# MCU.net
KiCad netlist of a schematic drawn in Altium Designer
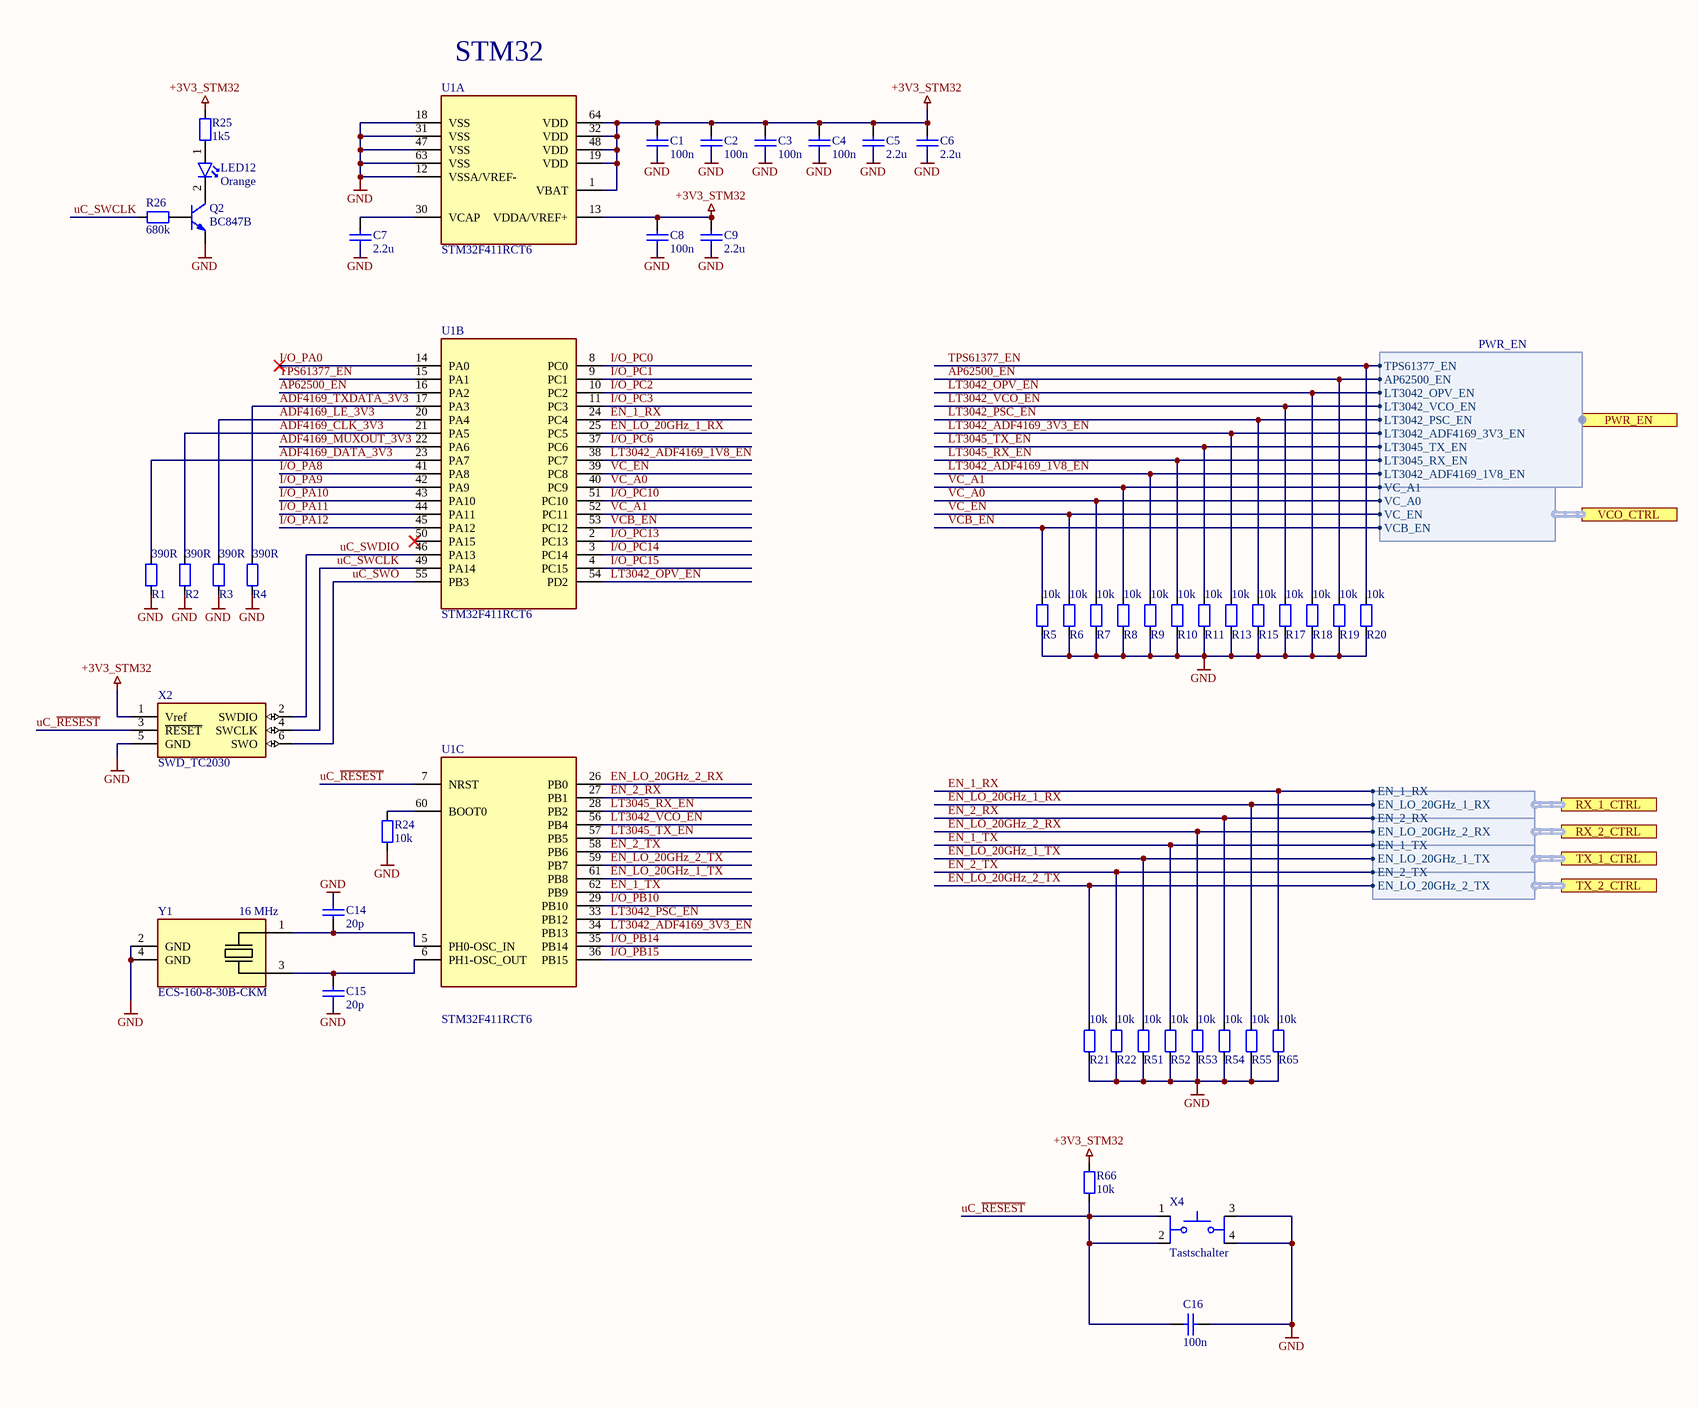
[diagram p0: MCU.SchDoc, left]
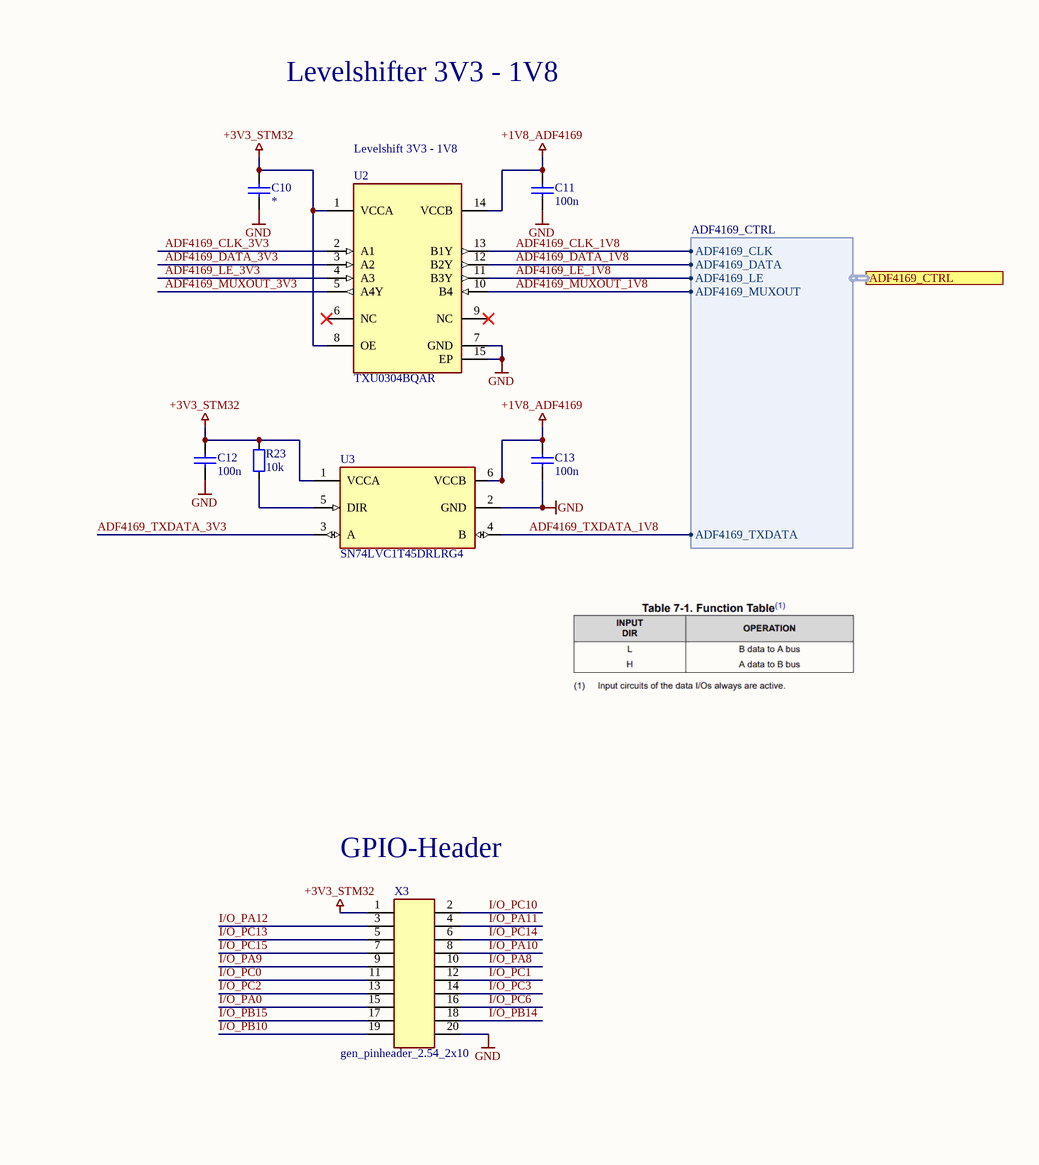
[diagram p1: MCU.SchDoc, right]

(export (version "E")
  (design (tool "Eeschema 10.0.6"))
  (components
    (comp (ref "C1")
      (value "100n")
      (footprint "C_0402_1005Metric_IPC_N")
      (description "Generic MLCC with 0402 Footprint")
      (fields (field (name "TOLERANCE") "10%"))
      (libsource (lib "database_library") (part "Capacitor_unpol"))
    )
    (comp (ref "C2")
      (value "100n")
      (footprint "C_0402_1005Metric_IPC_N")
      (description "Generic MLCC with 0402 Footprint")
      (fields (field (name "TOLERANCE") "10%"))
      (libsource (lib "database_library") (part "Capacitor_unpol"))
    )
    (comp (ref "C3")
      (value "100n")
      (footprint "C_0402_1005Metric_IPC_N")
      (description "Generic MLCC with 0402 Footprint")
      (fields (field (name "TOLERANCE") "10%"))
      (libsource (lib "database_library") (part "Capacitor_unpol"))
    )
    (comp (ref "C4")
      (value "100n")
      (footprint "C_0402_1005Metric_IPC_N")
      (description "Generic MLCC with 0402 Footprint")
      (fields (field (name "TOLERANCE") "10%"))
      (libsource (lib "database_library") (part "Capacitor_unpol"))
    )
    (comp (ref "C5")
      (value "2.2u")
      (footprint "C_0603_1608Metric_IPC_N")
      (description "Generic MLCC with 0603 Footprint")
      (libsource (lib "database_library") (part "Capacitor_unpol"))
    )
    (comp (ref "C6")
      (value "2.2u")
      (footprint "C_0603_1608Metric_IPC_N")
      (description "Generic MLCC with 0603 Footprint")
      (libsource (lib "database_library") (part "Capacitor_unpol"))
    )
    (comp (ref "C7")
      (value "2.2u")
      (footprint "C_0603_1608Metric_IPC_N")
      (description "Generic MLCC with 0603 Footprint")
      (libsource (lib "database_library") (part "Capacitor_unpol"))
    )
    (comp (ref "C8")
      (value "100n")
      (footprint "C_0402_1005Metric_IPC_N")
      (description "Generic MLCC with 0402 Footprint")
      (fields (field (name "TOLERANCE") "10%"))
      (libsource (lib "database_library") (part "Capacitor_unpol"))
    )
    (comp (ref "C9")
      (value "2.2u")
      (footprint "C_0603_1608Metric_IPC_N")
      (description "Generic MLCC with 0603 Footprint")
      (libsource (lib "database_library") (part "Capacitor_unpol"))
    )
    (comp (ref "C10")
      (value "*")
      (footprint "C_0402_1005Metric_IPC_N")
      (description "Generic MLCC with 0402 Footprint")
      (libsource (lib "database_library") (part "Capacitor_unpol"))
    )
    (comp (ref "C11")
      (value "100n")
      (footprint "C_0402_1005Metric_IPC_N")
      (description "Generic MLCC with 0402 Footprint")
      (fields (field (name "TOLERANCE") "10%"))
      (libsource (lib "database_library") (part "Capacitor_unpol"))
    )
    (comp (ref "C12")
      (value "100n")
      (footprint "C_0402_1005Metric_IPC_N")
      (description "Generic MLCC with 0402 Footprint")
      (fields (field (name "TOLERANCE") "10%"))
      (libsource (lib "database_library") (part "Capacitor_unpol"))
    )
    (comp (ref "C13")
      (value "100n")
      (footprint "C_0402_1005Metric_IPC_N")
      (description "Generic MLCC with 0402 Footprint")
      (fields (field (name "TOLERANCE") "10%"))
      (libsource (lib "database_library") (part "Capacitor_unpol"))
    )
    (comp (ref "C14")
      (value "20p")
      (footprint "C_0402_1005Metric_IPC_N")
      (description "Generic MLCC with 0402 Footprint")
      (libsource (lib "database_library") (part "Capacitor_unpol"))
    )
    (comp (ref "C15")
      (value "20p")
      (footprint "C_0402_1005Metric_IPC_N")
      (description "Generic MLCC with 0402 Footprint")
      (libsource (lib "database_library") (part "Capacitor_unpol"))
    )
    (comp (ref "C16")
      (value "100n")
      (footprint "C_0402_1005Metric_IPC_N")
      (description "Generic MLCC with 0402 Footprint")
      (libsource (lib "database_library") (part "Capacitor_unpol"))
    )
    (comp (ref "LED12")
      (value "Orange")
      (footprint "LED_0603_1806Metric_IPC_N")
      (description "MLCC, Low Current, Orange, 2.2V, 20mA, 0603")
      (fields
        (field (name "MANUFACTURER") "Broadcom / Avago")
        (field (name "MANUFACTURER PART NUMBER") "HSMD-C190")
      )
      (libsource (lib "database_library") (part "LED"))
    )
    (comp (ref "Q2")
      (value "BC847B")
      (footprint "SOT-23-3")
      (fields (field (name "MANUFACTURER") "Diotec Semiconductor"))
      (libsource (lib "database_library") (part "NPN"))
    )
    (comp (ref "R1")
      (value "390R")
      (footprint "R_0402_1005Metric_IPC_N")
      (description "Generic Chip Resistor with 0402 Footprint")
      (libsource (lib "database_library") (part "Resistor"))
    )
    (comp (ref "R2")
      (value "390R")
      (footprint "R_0402_1005Metric_IPC_N")
      (description "Generic Chip Resistor with 0402 Footprint")
      (libsource (lib "database_library") (part "Resistor"))
    )
    (comp (ref "R3")
      (value "390R")
      (footprint "R_0402_1005Metric_IPC_N")
      (description "Generic Chip Resistor with 0402 Footprint")
      (libsource (lib "database_library") (part "Resistor"))
    )
    (comp (ref "R4")
      (value "390R")
      (footprint "R_0402_1005Metric_IPC_N")
      (description "Generic Chip Resistor with 0402 Footprint")
      (libsource (lib "database_library") (part "Resistor"))
    )
    (comp (ref "R5")
      (value "10k")
      (footprint "R_0402_1005Metric_IPC_N")
      (description "Generic Chip Resistor with 0402 Footprint")
      (libsource (lib "database_library") (part "Resistor"))
    )
    (comp (ref "R6")
      (value "10k")
      (footprint "R_0402_1005Metric_IPC_N")
      (description "Generic Chip Resistor with 0402 Footprint")
      (libsource (lib "database_library") (part "Resistor"))
    )
    (comp (ref "R7")
      (value "10k")
      (footprint "R_0402_1005Metric_IPC_N")
      (description "Generic Chip Resistor with 0402 Footprint")
      (libsource (lib "database_library") (part "Resistor"))
    )
    (comp (ref "R8")
      (value "10k")
      (footprint "R_0402_1005Metric_IPC_N")
      (description "Generic Chip Resistor with 0402 Footprint")
      (libsource (lib "database_library") (part "Resistor"))
    )
    (comp (ref "R9")
      (value "10k")
      (footprint "R_0402_1005Metric_IPC_N")
      (description "Generic Chip Resistor with 0402 Footprint")
      (libsource (lib "database_library") (part "Resistor"))
    )
    (comp (ref "R10")
      (value "10k")
      (footprint "R_0402_1005Metric_IPC_N")
      (description "Generic Chip Resistor with 0402 Footprint")
      (libsource (lib "database_library") (part "Resistor"))
    )
    (comp (ref "R11")
      (value "10k")
      (footprint "R_0402_1005Metric_IPC_N")
      (description "Generic Chip Resistor with 0402 Footprint")
      (libsource (lib "database_library") (part "Resistor"))
    )
    (comp (ref "R13")
      (value "10k")
      (footprint "R_0402_1005Metric_IPC_N")
      (description "Generic Chip Resistor with 0402 Footprint")
      (libsource (lib "database_library") (part "Resistor"))
    )
    (comp (ref "R15")
      (value "10k")
      (footprint "R_0402_1005Metric_IPC_N")
      (description "Generic Chip Resistor with 0402 Footprint")
      (libsource (lib "database_library") (part "Resistor"))
    )
    (comp (ref "R17")
      (value "10k")
      (footprint "R_0402_1005Metric_IPC_N")
      (description "Generic Chip Resistor with 0402 Footprint")
      (libsource (lib "database_library") (part "Resistor"))
    )
    (comp (ref "R18")
      (value "10k")
      (footprint "R_0402_1005Metric_IPC_N")
      (description "Generic Chip Resistor with 0402 Footprint")
      (libsource (lib "database_library") (part "Resistor"))
    )
    (comp (ref "R19")
      (value "10k")
      (footprint "R_0402_1005Metric_IPC_N")
      (description "Generic Chip Resistor with 0402 Footprint")
      (libsource (lib "database_library") (part "Resistor"))
    )
    (comp (ref "R20")
      (value "10k")
      (footprint "R_0402_1005Metric_IPC_N")
      (description "Generic Chip Resistor with 0402 Footprint")
      (libsource (lib "database_library") (part "Resistor"))
    )
    (comp (ref "R21")
      (value "10k")
      (footprint "R_0402_1005Metric_IPC_N")
      (description "Generic Chip Resistor with 0402 Footprint")
      (libsource (lib "database_library") (part "Resistor"))
    )
    (comp (ref "R22")
      (value "10k")
      (footprint "R_0402_1005Metric_IPC_N")
      (description "Generic Chip Resistor with 0402 Footprint")
      (libsource (lib "database_library") (part "Resistor"))
    )
    (comp (ref "R23")
      (value "10k")
      (footprint "R_0402_1005Metric_IPC_N")
      (description "Generic Chip Resistor with 0402 Footprint")
      (libsource (lib "database_library") (part "Resistor"))
    )
    (comp (ref "R24")
      (value "10k")
      (footprint "R_0402_1005Metric_IPC_N")
      (description "Generic Chip Resistor with 0402 Footprint")
      (libsource (lib "database_library") (part "Resistor"))
    )
    (comp (ref "R25")
      (value "1k5")
      (footprint "R_0402_1005Metric_IPC_N")
      (description "Generic Chip Resistor with 0402 Footprint")
      (libsource (lib "database_library") (part "Resistor"))
    )
    (comp (ref "R26")
      (value "680k")
      (footprint "R_0402_1005Metric_IPC_N")
      (description "Generic Chip Resistor with 0402 Footprint")
      (libsource (lib "database_library") (part "Resistor"))
    )
    (comp (ref "R51")
      (value "10k")
      (footprint "R_0402_1005Metric_IPC_N")
      (description "Generic Chip Resistor with 0402 Footprint")
      (libsource (lib "database_library") (part "Resistor"))
    )
    (comp (ref "R52")
      (value "10k")
      (footprint "R_0402_1005Metric_IPC_N")
      (description "Generic Chip Resistor with 0402 Footprint")
      (libsource (lib "database_library") (part "Resistor"))
    )
    (comp (ref "R53")
      (value "10k")
      (footprint "R_0402_1005Metric_IPC_N")
      (description "Generic Chip Resistor with 0402 Footprint")
      (libsource (lib "database_library") (part "Resistor"))
    )
    (comp (ref "R54")
      (value "10k")
      (footprint "R_0402_1005Metric_IPC_N")
      (description "Generic Chip Resistor with 0402 Footprint")
      (libsource (lib "database_library") (part "Resistor"))
    )
    (comp (ref "R55")
      (value "10k")
      (footprint "R_0402_1005Metric_IPC_N")
      (description "Generic Chip Resistor with 0402 Footprint")
      (libsource (lib "database_library") (part "Resistor"))
    )
    (comp (ref "R65")
      (value "10k")
      (footprint "R_0402_1005Metric_IPC_N")
      (description "Generic Chip Resistor with 0402 Footprint")
      (libsource (lib "database_library") (part "Resistor"))
    )
    (comp (ref "R66")
      (value "10k")
      (footprint "R_0402_1005Metric_IPC_N")
      (description "Generic Chip Resistor with 0402 Footprint")
      (libsource (lib "database_library") (part "Resistor"))
    )
    (comp (ref "U1")
      (value "STM32F411RCT6")
      (footprint "QFP50P1200X1200X160-64N")
      (fields
        (field (name "MOUSER PART NUMBER") "511-STM32F411RCT6")
        (field (name "MANUFACTURER") "STMicroelectronics")
      )
      (libsource (lib "database_library") (part "STM32F411RCT6"))
    )
    (comp (ref "U2")
      (value "TXU0304BQAR")
      (footprint "WQFN-14-1EP_2.5x3mm_P0.5mm_EP1.0x1.5mm_IPC_N")
      (fields (field (name "MANUFACTURER") "Texas Instruments"))
      (libsource (lib "database_library") (part "TXU0304BQAR"))
    )
    (comp (ref "U3")
      (value "SN74LVC1T45DRLRG4")
      (footprint "SOTFL50P160X60-6N")
      (fields (field (name "MANUFACTURER") "Texas Instruments"))
      (libsource (lib "database_library") (part "SN74LVC1T45DRLRG4"))
    )
    (comp (ref "X2")
      (value "SWD_TC2030")
      (footprint "Tag-Connect_TC2030-IDC-FP_2x03_P1.27mm_Vertical")
      (fields
        (field (name "MANUFACTURER PART NUMBER") "SWD TC2030")
        (field (name "MANUFACTURER") "Tag-Connect")
      )
      (libsource (lib "database_library") (part "SWD_TC2030"))
    )
    (comp (ref "X3")
      (value "gen_pinheader_2.54_2x10")
      (footprint "Pinheader_2.54_2x10")
      (fields
        (field (name "MANUFACTURER PART NUMBER") "TSW-110-07-G-D")
        (field (name "MANUFACTURER") "Samtec")
      )
      (libsource (lib "database_library") (part "gen_pinheader_2.54_2x10"))
    )
    (comp (ref "X4")
      (value "Tastschalter")
      (footprint "TL3301AF160QG")
      (fields
        (field (name "MANUFACTURER PART NUMBER") "TL3301AF160QG")
        (field (name "MANUFACTURER") "E-Switch")
      )
      (libsource (lib "database_library") (part "Tastschalter"))
    )
    (comp (ref "Y1")
      (value "ECS-160-8-30B-CKM")
      (footprint "XTAL_SMD_5032_4Pin_5x3.2mm")
      (fields (field (name "MANUFACTURER") "ECS"))
      (libsource (lib "database_library") (part "XTAL_PIN1/3_GND2/4"))
    )
  )
  (nets
    (net (code "8") (name "+1V8_ADF4169") (class "Default")
      (node (ref "C11") (pin "2") (pinfunction "2_2") (pintype "passive"))
      (node (ref "C13") (pin "2") (pinfunction "2_2") (pintype "passive"))
      (node (ref "U2") (pin "14") (pinfunction "VCCB_14") (pintype "passive"))
      (node (ref "U3") (pin "6") (pinfunction "VCCB_6") (pintype "power_in"))
    )
    (net (code "9") (name "+3V3_STM32") (class "Default")
      (node (ref "C1") (pin "2") (pinfunction "2_2") (pintype "passive"))
      (node (ref "C10") (pin "2") (pinfunction "2_2") (pintype "passive"))
      (node (ref "C12") (pin "2") (pinfunction "2_2") (pintype "passive"))
      (node (ref "C2") (pin "2") (pinfunction "2_2") (pintype "passive"))
      (node (ref "C3") (pin "2") (pinfunction "2_2") (pintype "passive"))
      (node (ref "C4") (pin "2") (pinfunction "2_2") (pintype "passive"))
      (node (ref "C5") (pin "2") (pinfunction "2_2") (pintype "passive"))
      (node (ref "C6") (pin "2") (pinfunction "2_2") (pintype "passive"))
      (node (ref "C8") (pin "2") (pinfunction "2_2") (pintype "passive"))
      (node (ref "C9") (pin "2") (pinfunction "2_2") (pintype "passive"))
      (node (ref "R23") (pin "1") (pinfunction "1_1") (pintype "passive"))
      (node (ref "R25") (pin "2") (pinfunction "2_2") (pintype "passive"))
      (node (ref "R66") (pin "2") (pinfunction "2_2") (pintype "passive"))
      (node (ref "U1") (pin "1") (pinfunction "VBAT_1") (pintype "passive"))
      (node (ref "U1") (pin "13") (pinfunction "VDDA/VREF+_13") (pintype "passive"))
      (node (ref "U1") (pin "19") (pinfunction "VDD_19") (pintype "passive"))
      (node (ref "U1") (pin "32") (pinfunction "VDD_32") (pintype "passive"))
      (node (ref "U1") (pin "48") (pinfunction "VDD_48") (pintype "passive"))
      (node (ref "U1") (pin "64") (pinfunction "VDD_64") (pintype "passive"))
      (node (ref "U2") (pin "1") (pinfunction "VCCA_1") (pintype "passive"))
      (node (ref "U2") (pin "8") (pinfunction "OE_8") (pintype "passive"))
      (node (ref "U3") (pin "1") (pinfunction "VCCA_1") (pintype "power_in"))
      (node (ref "X2") (pin "1") (pinfunction "Vref_1") (pintype "passive"))
      (node (ref "X3") (pin "1") (pintype "passive"))
    )
    (net (code "10") (name "/ADF4169_CLK_1V8") (class "Default")
      (node (ref "U2") (pin "13") (pinfunction "B1Y_13") (pintype "output"))
    )
    (net (code "11") (name "/ADF4169_CLK_3V3") (class "Default")
      (node (ref "R2") (pin "2") (pinfunction "2_2") (pintype "passive"))
      (node (ref "U1") (pin "21") (pinfunction "PA5_21") (pintype "passive"))
      (node (ref "U2") (pin "2") (pinfunction "A1_2") (pintype "input"))
    )
    (net (code "12") (name "/ADF4169_DATA_1V8") (class "Default")
      (node (ref "U2") (pin "12") (pinfunction "B2Y_12") (pintype "output"))
    )
    (net (code "13") (name "/ADF4169_DATA_3V3") (class "Default")
      (node (ref "R1") (pin "2") (pinfunction "2_2") (pintype "passive"))
      (node (ref "U1") (pin "23") (pinfunction "PA7_23") (pintype "passive"))
      (node (ref "U2") (pin "3") (pinfunction "A2_3") (pintype "input"))
    )
    (net (code "14") (name "/ADF4169_LE_1V8") (class "Default")
      (node (ref "U2") (pin "11") (pinfunction "B3Y_11") (pintype "output"))
    )
    (net (code "15") (name "/ADF4169_LE_3V3") (class "Default")
      (node (ref "R3") (pin "2") (pinfunction "2_2") (pintype "passive"))
      (node (ref "U1") (pin "20") (pinfunction "PA4_20") (pintype "passive"))
      (node (ref "U2") (pin "4") (pinfunction "A3_4") (pintype "input"))
    )
    (net (code "16") (name "/ADF4169_MUXOUT_1V8") (class "Default")
      (node (ref "U2") (pin "10") (pinfunction "B4_10") (pintype "input"))
    )
    (net (code "17") (name "/ADF4169_MUXOUT_3V3") (class "Default")
      (node (ref "U1") (pin "22") (pinfunction "PA6_22") (pintype "passive"))
      (node (ref "U2") (pin "5") (pinfunction "A4Y_5") (pintype "output"))
    )
    (net (code "18") (name "/ADF4169_TXDATA_1V8") (class "Default")
      (node (ref "U3") (pin "4") (pinfunction "B_4") (pintype "bidirectional"))
    )
    (net (code "19") (name "/ADF4169_TXDATA_3V3") (class "Default")
      (node (ref "R4") (pin "2") (pinfunction "2_2") (pintype "passive"))
      (node (ref "U1") (pin "17") (pinfunction "PA3_17") (pintype "passive"))
      (node (ref "U3") (pin "3") (pinfunction "A_3") (pintype "bidirectional"))
    )
    (net (code "20") (name "/AP62500_EN") (class "Default")
      (node (ref "R19") (pin "2") (pinfunction "2_2") (pintype "passive"))
      (node (ref "U1") (pin "16") (pinfunction "PA2_16") (pintype "passive"))
    )
    (net (code "21") (name "/EN_1_RX") (class "Default")
      (node (ref "R65") (pin "2") (pinfunction "2_2") (pintype "passive"))
      (node (ref "U1") (pin "24") (pinfunction "PC4_24") (pintype "passive"))
    )
    (net (code "22") (name "/EN_1_TX") (class "Default")
      (node (ref "R52") (pin "2") (pinfunction "2_2") (pintype "passive"))
      (node (ref "U1") (pin "62") (pinfunction "PB9_62") (pintype "passive"))
    )
    (net (code "23") (name "/EN_2_RX") (class "Default")
      (node (ref "R54") (pin "2") (pinfunction "2_2") (pintype "passive"))
      (node (ref "U1") (pin "27") (pinfunction "PB1_27") (pintype "passive"))
    )
    (net (code "24") (name "/EN_2_TX") (class "Default")
      (node (ref "R22") (pin "2") (pinfunction "2_2") (pintype "passive"))
      (node (ref "U1") (pin "58") (pinfunction "PB6_58") (pintype "passive"))
    )
    (net (code "25") (name "/EN_LO_20GHz_1_RX") (class "Default")
      (node (ref "R55") (pin "2") (pinfunction "2_2") (pintype "passive"))
      (node (ref "U1") (pin "25") (pinfunction "PC5_25") (pintype "passive"))
    )
    (net (code "26") (name "/EN_LO_20GHz_1_TX") (class "Default")
      (node (ref "R51") (pin "2") (pinfunction "2_2") (pintype "passive"))
      (node (ref "U1") (pin "61") (pinfunction "PB8_61") (pintype "passive"))
    )
    (net (code "27") (name "/EN_LO_20GHz_2_RX") (class "Default")
      (node (ref "R53") (pin "2") (pinfunction "2_2") (pintype "passive"))
      (node (ref "U1") (pin "26") (pinfunction "PB0_26") (pintype "passive"))
    )
    (net (code "28") (name "/EN_LO_20GHz_2_TX") (class "Default")
      (node (ref "R21") (pin "2") (pinfunction "2_2") (pintype "passive"))
      (node (ref "U1") (pin "59") (pinfunction "PB7_59") (pintype "passive"))
    )
    (net (code "29") (name "/I{slash}O_PA0") (class "Default")
      (node (ref "U1") (pin "14") (pinfunction "PA0_14") (pintype "passive"))
      (node (ref "X3") (pin "15") (pintype "passive"))
    )
    (net (code "30") (name "/I{slash}O_PA8") (class "Default")
      (node (ref "U1") (pin "41") (pinfunction "PA8_41") (pintype "passive"))
      (node (ref "X3") (pin "10") (pintype "passive"))
    )
    (net (code "31") (name "/I{slash}O_PA9") (class "Default")
      (node (ref "U1") (pin "42") (pinfunction "PA9_42") (pintype "passive"))
      (node (ref "X3") (pin "9") (pintype "passive"))
    )
    (net (code "32") (name "/I{slash}O_PA10") (class "Default")
      (node (ref "U1") (pin "43") (pinfunction "PA10_43") (pintype "passive"))
      (node (ref "X3") (pin "8") (pintype "passive"))
    )
    (net (code "33") (name "/I{slash}O_PA11") (class "Default")
      (node (ref "U1") (pin "44") (pinfunction "PA11_44") (pintype "passive"))
      (node (ref "X3") (pin "4") (pintype "passive"))
    )
    (net (code "34") (name "/I{slash}O_PA12") (class "Default")
      (node (ref "U1") (pin "45") (pinfunction "PA12_45") (pintype "passive"))
      (node (ref "X3") (pin "3") (pintype "passive"))
    )
    (net (code "35") (name "/I{slash}O_PB10") (class "Default")
      (node (ref "U1") (pin "29") (pinfunction "PB10_29") (pintype "passive"))
      (node (ref "X3") (pin "19") (pintype "passive"))
    )
    (net (code "36") (name "/I{slash}O_PB14") (class "Default")
      (node (ref "U1") (pin "35") (pinfunction "PB14_35") (pintype "passive"))
      (node (ref "X3") (pin "18") (pintype "passive"))
    )
    (net (code "37") (name "/I{slash}O_PB15") (class "Default")
      (node (ref "U1") (pin "36") (pinfunction "PB15_36") (pintype "passive"))
      (node (ref "X3") (pin "17") (pintype "passive"))
    )
    (net (code "38") (name "/I{slash}O_PC0") (class "Default")
      (node (ref "U1") (pin "8") (pinfunction "PC0_8") (pintype "passive"))
      (node (ref "X3") (pin "11") (pintype "passive"))
    )
    (net (code "39") (name "/I{slash}O_PC1") (class "Default")
      (node (ref "U1") (pin "9") (pinfunction "PC1_9") (pintype "passive"))
      (node (ref "X3") (pin "12") (pintype "passive"))
    )
    (net (code "40") (name "/I{slash}O_PC2") (class "Default")
      (node (ref "U1") (pin "10") (pinfunction "PC2_10") (pintype "passive"))
      (node (ref "X3") (pin "13") (pintype "passive"))
    )
    (net (code "41") (name "/I{slash}O_PC3") (class "Default")
      (node (ref "U1") (pin "11") (pinfunction "PC3_11") (pintype "passive"))
      (node (ref "X3") (pin "14") (pintype "passive"))
    )
    (net (code "42") (name "/I{slash}O_PC6") (class "Default")
      (node (ref "U1") (pin "37") (pinfunction "PC6_37") (pintype "passive"))
      (node (ref "X3") (pin "16") (pintype "passive"))
    )
    (net (code "43") (name "/I{slash}O_PC10") (class "Default")
      (node (ref "U1") (pin "51") (pinfunction "PC10_51") (pintype "passive"))
      (node (ref "X3") (pin "2") (pintype "passive"))
    )
    (net (code "44") (name "/I{slash}O_PC13") (class "Default")
      (node (ref "U1") (pin "2") (pinfunction "PC13_2") (pintype "passive"))
      (node (ref "X3") (pin "5") (pintype "passive"))
    )
    (net (code "45") (name "/I{slash}O_PC14") (class "Default")
      (node (ref "U1") (pin "3") (pinfunction "PC14_3") (pintype "passive"))
      (node (ref "X3") (pin "6") (pintype "passive"))
    )
    (net (code "46") (name "/I{slash}O_PC15") (class "Default")
      (node (ref "U1") (pin "4") (pinfunction "PC15_4") (pintype "passive"))
      (node (ref "X3") (pin "7") (pintype "passive"))
    )
    (net (code "47") (name "/LT3042_ADF4169_1V8_EN") (class "Default")
      (node (ref "R9") (pin "2") (pinfunction "2_2") (pintype "passive"))
      (node (ref "U1") (pin "38") (pinfunction "PC7_38") (pintype "passive"))
    )
    (net (code "48") (name "/LT3042_ADF4169_3V3_EN") (class "Default")
      (node (ref "R13") (pin "2") (pinfunction "2_2") (pintype "passive"))
      (node (ref "U1") (pin "34") (pinfunction "PB13_34") (pintype "passive"))
    )
    (net (code "49") (name "/LT3042_OPV_EN") (class "Default")
      (node (ref "R18") (pin "2") (pinfunction "2_2") (pintype "passive"))
      (node (ref "U1") (pin "54") (pinfunction "PD2_54") (pintype "passive"))
    )
    (net (code "50") (name "/LT3042_PSC_EN") (class "Default")
      (node (ref "R15") (pin "2") (pinfunction "2_2") (pintype "passive"))
      (node (ref "U1") (pin "33") (pinfunction "PB12_33") (pintype "passive"))
    )
    (net (code "51") (name "/LT3042_VCO_EN") (class "Default")
      (node (ref "R17") (pin "2") (pinfunction "2_2") (pintype "passive"))
      (node (ref "U1") (pin "56") (pinfunction "PB4_56") (pintype "passive"))
    )
    (net (code "52") (name "/LT3045_RX_EN") (class "Default")
      (node (ref "R10") (pin "2") (pinfunction "2_2") (pintype "passive"))
      (node (ref "U1") (pin "28") (pinfunction "PB2_28") (pintype "passive"))
    )
    (net (code "53") (name "/LT3045_TX_EN") (class "Default")
      (node (ref "R11") (pin "2") (pinfunction "2_2") (pintype "passive"))
      (node (ref "U1") (pin "57") (pinfunction "PB5_57") (pintype "passive"))
    )
    (net (code "54") (name "/TPS61377_EN") (class "Default")
      (node (ref "R20") (pin "2") (pinfunction "2_2") (pintype "passive"))
      (node (ref "U1") (pin "15") (pinfunction "PA1_15") (pintype "passive"))
    )
    (net (code "55") (name "/VCB_EN") (class "Default")
      (node (ref "R5") (pin "2") (pinfunction "2_2") (pintype "passive"))
      (node (ref "U1") (pin "53") (pinfunction "PC12_53") (pintype "passive"))
    )
    (net (code "56") (name "/VC_A0") (class "Default")
      (node (ref "R7") (pin "2") (pinfunction "2_2") (pintype "passive"))
      (node (ref "U1") (pin "40") (pinfunction "PC9_40") (pintype "passive"))
    )
    (net (code "57") (name "/VC_A1") (class "Default")
      (node (ref "R8") (pin "2") (pinfunction "2_2") (pintype "passive"))
      (node (ref "U1") (pin "52") (pinfunction "PC11_52") (pintype "passive"))
    )
    (net (code "58") (name "/VC_EN") (class "Default")
      (node (ref "R6") (pin "2") (pinfunction "2_2") (pintype "passive"))
      (node (ref "U1") (pin "39") (pinfunction "PC8_39") (pintype "passive"))
    )
    (net (code "59") (name "/uC_SWCLK") (class "Default")
      (node (ref "R26") (pin "1") (pinfunction "1_1") (pintype "passive"))
      (node (ref "U1") (pin "49") (pinfunction "PA14_49") (pintype "passive"))
      (node (ref "X2") (pin "4") (pinfunction "SWCLK_4") (pintype "bidirectional"))
    )
    (net (code "60") (name "/uC_SWDIO") (class "Default")
      (node (ref "U1") (pin "46") (pinfunction "PA13_46") (pintype "passive"))
      (node (ref "X2") (pin "2") (pinfunction "SWDIO_2") (pintype "bidirectional"))
    )
    (net (code "61") (name "/uC_SWO") (class "Default")
      (node (ref "U1") (pin "55") (pinfunction "PB3_55") (pintype "passive"))
      (node (ref "X2") (pin "6") (pinfunction "SWO_6") (pintype "bidirectional"))
    )
    (net (code "62") (name "/uC_~{RESEST}") (class "Default")
      (node (ref "C16") (pin "1") (pinfunction "1_1") (pintype "passive"))
      (node (ref "R66") (pin "1") (pinfunction "1_1") (pintype "passive"))
      (node (ref "U1") (pin "7") (pinfunction "NRST_7") (pintype "passive"))
      (node (ref "X2") (pin "3") (pinfunction "~{RESET}_3") (pintype "passive"))
      (node (ref "X4") (pin "1") (pinfunction "1_1") (pintype "passive"))
      (node (ref "X4") (pin "2") (pinfunction "2_2") (pintype "passive"))
    )
    (net (code "70") (name "GND") (class "Default")
      (node (ref "C1") (pin "1") (pinfunction "1_1") (pintype "passive"))
      (node (ref "C10") (pin "1") (pinfunction "1_1") (pintype "passive"))
      (node (ref "C11") (pin "1") (pinfunction "1_1") (pintype "passive"))
      (node (ref "C12") (pin "1") (pinfunction "1_1") (pintype "passive"))
      (node (ref "C13") (pin "1") (pinfunction "1_1") (pintype "passive"))
      (node (ref "C14") (pin "2") (pinfunction "2_2") (pintype "passive"))
      (node (ref "C15") (pin "1") (pinfunction "1_1") (pintype "passive"))
      (node (ref "C16") (pin "2") (pinfunction "2_2") (pintype "passive"))
      (node (ref "C2") (pin "1") (pinfunction "1_1") (pintype "passive"))
      (node (ref "C3") (pin "1") (pinfunction "1_1") (pintype "passive"))
      (node (ref "C4") (pin "1") (pinfunction "1_1") (pintype "passive"))
      (node (ref "C5") (pin "1") (pinfunction "1_1") (pintype "passive"))
      (node (ref "C6") (pin "1") (pinfunction "1_1") (pintype "passive"))
      (node (ref "C7") (pin "1") (pinfunction "1_1") (pintype "passive"))
      (node (ref "C8") (pin "1") (pinfunction "1_1") (pintype "passive"))
      (node (ref "C9") (pin "1") (pinfunction "1_1") (pintype "passive"))
      (node (ref "Q2") (pin "2") (pinfunction "E_2") (pintype "passive"))
      (node (ref "R1") (pin "1") (pinfunction "1_1") (pintype "passive"))
      (node (ref "R10") (pin "1") (pinfunction "1_1") (pintype "passive"))
      (node (ref "R11") (pin "1") (pinfunction "1_1") (pintype "passive"))
      (node (ref "R13") (pin "1") (pinfunction "1_1") (pintype "passive"))
      (node (ref "R15") (pin "1") (pinfunction "1_1") (pintype "passive"))
      (node (ref "R17") (pin "1") (pinfunction "1_1") (pintype "passive"))
      (node (ref "R18") (pin "1") (pinfunction "1_1") (pintype "passive"))
      (node (ref "R19") (pin "1") (pinfunction "1_1") (pintype "passive"))
      (node (ref "R2") (pin "1") (pinfunction "1_1") (pintype "passive"))
      (node (ref "R20") (pin "1") (pinfunction "1_1") (pintype "passive"))
      (node (ref "R21") (pin "1") (pinfunction "1_1") (pintype "passive"))
      (node (ref "R22") (pin "1") (pinfunction "1_1") (pintype "passive"))
      (node (ref "R24") (pin "2") (pinfunction "2_2") (pintype "passive"))
      (node (ref "R3") (pin "1") (pinfunction "1_1") (pintype "passive"))
      (node (ref "R4") (pin "1") (pinfunction "1_1") (pintype "passive"))
      (node (ref "R5") (pin "1") (pinfunction "1_1") (pintype "passive"))
      (node (ref "R51") (pin "1") (pinfunction "1_1") (pintype "passive"))
      (node (ref "R52") (pin "1") (pinfunction "1_1") (pintype "passive"))
      (node (ref "R53") (pin "1") (pinfunction "1_1") (pintype "passive"))
      (node (ref "R54") (pin "1") (pinfunction "1_1") (pintype "passive"))
      (node (ref "R55") (pin "1") (pinfunction "1_1") (pintype "passive"))
      (node (ref "R6") (pin "1") (pinfunction "1_1") (pintype "passive"))
      (node (ref "R65") (pin "1") (pinfunction "1_1") (pintype "passive"))
      (node (ref "R7") (pin "1") (pinfunction "1_1") (pintype "passive"))
      (node (ref "R8") (pin "1") (pinfunction "1_1") (pintype "passive"))
      (node (ref "R9") (pin "1") (pinfunction "1_1") (pintype "passive"))
      (node (ref "U1") (pin "12") (pinfunction "VSSA/VREF-_12") (pintype "passive"))
      (node (ref "U1") (pin "18") (pinfunction "VSS_18") (pintype "passive"))
      (node (ref "U1") (pin "31") (pinfunction "VSS_31") (pintype "passive"))
      (node (ref "U1") (pin "47") (pinfunction "VSS_47") (pintype "passive"))
      (node (ref "U1") (pin "63") (pinfunction "VSS_63") (pintype "passive"))
      (node (ref "U2") (pin "15") (pinfunction "EP_15") (pintype "passive"))
      (node (ref "U2") (pin "7") (pinfunction "GND_7") (pintype "passive"))
      (node (ref "U3") (pin "2") (pinfunction "GND_2") (pintype "power_in"))
      (node (ref "X2") (pin "5") (pinfunction "GND_5") (pintype "passive"))
      (node (ref "X3") (pin "20") (pintype "passive"))
      (node (ref "X4") (pin "3") (pinfunction "3_3") (pintype "passive"))
      (node (ref "X4") (pin "4") (pinfunction "4_4") (pintype "passive"))
      (node (ref "Y1") (pin "2") (pinfunction "GND_2") (pintype "power_in"))
      (node (ref "Y1") (pin "4") (pinfunction "GND_4") (pintype "power_in"))
    )
    (net (code "71") (name "Net-(LED12-Pad1)") (class "Default")
      (node (ref "LED12") (pin "1") (pinfunction "1_1") (pintype "passive"))
      (node (ref "R25") (pin "1") (pinfunction "1_1") (pintype "passive"))
    )
    (net (code "72") (name "Net-(Q2-B)") (class "Default")
      (node (ref "Q2") (pin "1") (pinfunction "B_1") (pintype "passive"))
      (node (ref "R26") (pin "2") (pinfunction "2_2") (pintype "passive"))
    )
    (net (code "73") (name "Net-(Q2-C)") (class "Default")
      (node (ref "LED12") (pin "2") (pinfunction "2_2") (pintype "passive"))
      (node (ref "Q2") (pin "3") (pinfunction "C_3") (pintype "passive"))
    )
    (net (code "74") (name "Net-(U1A-VCAP)") (class "Default")
      (node (ref "C7") (pin "2") (pinfunction "2_2") (pintype "passive"))
      (node (ref "U1") (pin "30") (pinfunction "VCAP_30") (pintype "passive"))
    )
    (net (code "75") (name "Net-(U1C-BOOT0)") (class "Default")
      (node (ref "R24") (pin "1") (pinfunction "1_1") (pintype "passive"))
      (node (ref "U1") (pin "60") (pinfunction "BOOT0_60") (pintype "passive"))
    )
    (net (code "76") (name "Net-(U1C-PH0-OSC_IN)") (class "Default")
      (node (ref "C14") (pin "1") (pinfunction "1_1") (pintype "passive"))
      (node (ref "U1") (pin "5") (pinfunction "PH0-OSC_IN_5") (pintype "passive"))
      (node (ref "Y1") (pin "1") (pinfunction "IN/OUT_1") (pintype "passive"))
    )
    (net (code "77") (name "Net-(U1C-PH1-OSC_OUT)") (class "Default")
      (node (ref "C15") (pin "2") (pinfunction "2_2") (pintype "passive"))
      (node (ref "U1") (pin "6") (pinfunction "PH1-OSC_OUT_6") (pintype "passive"))
      (node (ref "Y1") (pin "3") (pinfunction "IN/OUT_3") (pintype "passive"))
    )
    (net (code "78") (name "Net-(U3-DIR)") (class "Default")
      (node (ref "R23") (pin "2") (pinfunction "2_2") (pintype "passive"))
      (node (ref "U3") (pin "5") (pinfunction "DIR_5") (pintype "input"))
    )
    (net (code "79") (name "unconnected-(U1B-PA15-Pad50)") (class "Default")
      (node (ref "U1") (pin "50") (pinfunction "PA15_50") (pintype "passive+no_connect"))
    )
    (net (code "80") (name "unconnected-(U2-NC-Pad6)") (class "Default")
      (node (ref "U2") (pin "6") (pinfunction "NC_6") (pintype "passive+no_connect"))
    )
    (net (code "81") (name "unconnected-(U2-NC-Pad9)") (class "Default")
      (node (ref "U2") (pin "9") (pinfunction "NC_9") (pintype "passive+no_connect"))
    )
  )
)
